# dawn.net
KiCad netlist of a schematic drawn in EAGLE
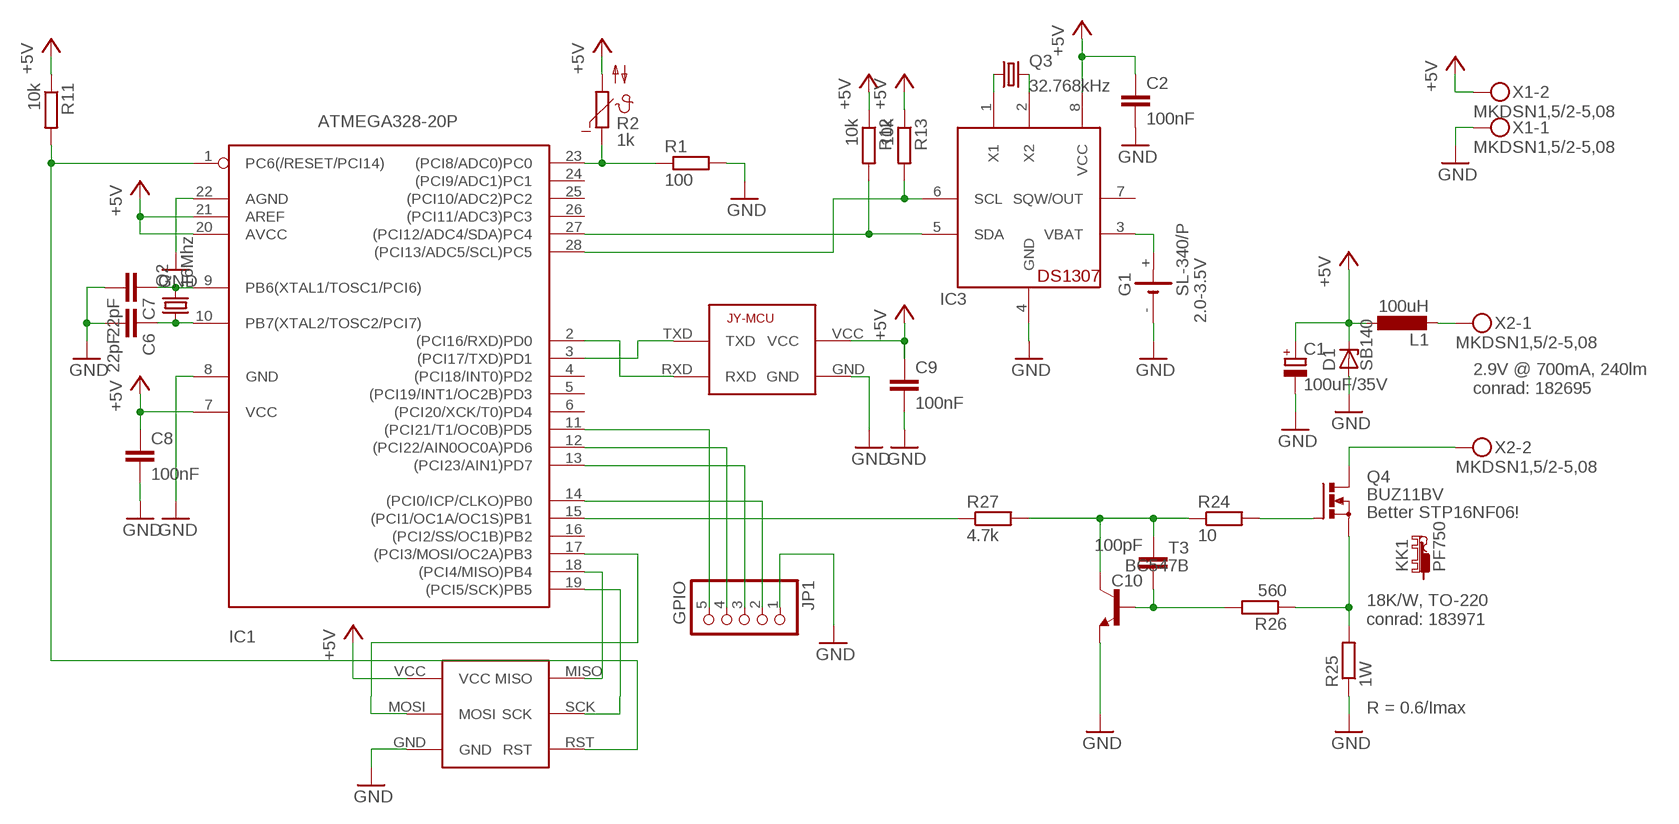
[diagram p0: schematic, sheet 1]

(export (version "E")
  (design (tool "Eeschema 10.0.6"))
  (components
    (comp (ref "C1")
      (value "100uF/35V")
      (footprint "eagle-import:E5-6")
      (libsource (lib "eagle-import") (part "CPOL-EUE5-6"))
    )
    (comp (ref "C2")
      (value "100nF")
      (footprint "eagle-import:C025-025X050")
      (libsource (lib "eagle-import") (part "C-EU025-025X050"))
    )
    (comp (ref "C6")
      (value "22pF")
      (footprint "eagle-import:C050-025X075")
      (libsource (lib "eagle-import") (part "C-EU050-025X075"))
    )
    (comp (ref "C7")
      (value "22pF")
      (footprint "eagle-import:C025-025X050")
      (libsource (lib "eagle-import") (part "C-EU025-025X050"))
    )
    (comp (ref "C8")
      (value "100nF")
      (footprint "eagle-import:C025-025X050")
      (libsource (lib "eagle-import") (part "C-EU025-025X050"))
    )
    (comp (ref "C9")
      (value "100nF")
      (footprint "eagle-import:C025-025X050")
      (libsource (lib "eagle-import") (part "C-EU025-025X050"))
    )
    (comp (ref "C10")
      (value "100pF")
      (footprint "eagle-import:C025-025X050")
      (libsource (lib "eagle-import") (part "C-EU025-025X050"))
    )
    (comp (ref "D1")
      (value "SB140")
      (footprint "eagle-import:DO35Z10")
      (libsource (lib "eagle-import") (part "ZENER-DIODEDO35Z10"))
    )
    (comp (ref "G1")
      (value "SL-340/P")
      (footprint "eagle-import:BEL_P")
      (libsource (lib "eagle-import") (part "SL-340/P"))
    )
    (comp (ref "IC1")
      (value "ATMEGA328-20P")
      (footprint "eagle-import:DIL28-3")
      (libsource (lib "eagle-import") (part "ATMEGA328P-20"))
    )
    (comp (ref "IC3")
      (value "DS1307")
      (footprint "eagle-import:DIL08")
      (libsource (lib "eagle-import") (part "DS1307"))
    )
    (comp (ref "JP1")
      (value "GPIO")
      (footprint "eagle-import:1X05")
      (libsource (lib "eagle-import") (part "PINHD-1X5"))
    )
    (comp (ref "KK1")
      (value "PF750")
      (footprint "eagle-import:PF752")
      (libsource (lib "eagle-import") (part "PF750"))
    )
    (comp (ref "L1")
      (value "100uH")
      (footprint "eagle-import:6000-XXXX-RC")
      (libsource (lib "eagle-import") (part "L-EU6000-XXX-RC"))
    )
    (comp (ref "Q2")
      (value "16Mhz")
      (footprint "eagle-import:HC18U-V")
      (libsource (lib "eagle-import") (part "CRYSTALHC18U-V"))
    )
    (comp (ref "Q3")
      (value "32.768kHz")
      (footprint "eagle-import:TC26V")
      (libsource (lib "eagle-import") (part "CRYSTALTC26V"))
    )
    (comp (ref "Q4")
      (value "BUZ11BV")
      (footprint "eagle-import:TO220BV")
      (libsource (lib "eagle-import") (part "BUZ11BV"))
    )
    (comp (ref "R1")
      (value "100")
      (footprint "eagle-import:0204V")
      (libsource (lib "eagle-import") (part "R-EU_0204/2V"))
    )
    (comp (ref "R2")
      (value "1k")
      (footprint "eagle-import:B57164")
      (fields (field (name "MPN") "B57164K474K52"))
      (libsource (lib "eagle-import") (part "B57164"))
    )
    (comp (ref "R11")
      (value "10k")
      (footprint "eagle-import:0207_10")
      (libsource (lib "eagle-import") (part "R-EU_0207/10"))
    )
    (comp (ref "R12")
      (value "10k")
      (footprint "eagle-import:0204_5")
      (libsource (lib "eagle-import") (part "R-EU_0204/5"))
    )
    (comp (ref "R13")
      (value "10k")
      (footprint "eagle-import:0204V")
      (libsource (lib "eagle-import") (part "R-EU_0204/2V"))
    )
    (comp (ref "R24")
      (value "10")
      (footprint "eagle-import:0204_7")
      (libsource (lib "eagle-import") (part "R-EU_0204/7"))
    )
    (comp (ref "R25")
      (value "1W")
      (footprint "eagle-import:0411_12")
      (libsource (lib "eagle-import") (part "R-EU_0411/12"))
    )
    (comp (ref "R26")
      (value "560")
      (footprint "eagle-import:0207_17")
      (libsource (lib "eagle-import") (part "R-EU_0207/17"))
    )
    (comp (ref "R27")
      (value "4.7k")
      (footprint "eagle-import:0207_10")
      (libsource (lib "eagle-import") (part "R-EU_0207/10"))
    )
    (comp (ref "T3")
      (value "BC547B")
      (footprint "eagle-import:TO92-EBC")
      (libsource (lib "eagle-import") (part "-NPN-TO92-EBC"))
    )
    (comp (ref "U$1")
      (value "JY-MCU")
      (footprint "eagle-import:JY-MCU")
      (libsource (lib "eagle-import") (part "JY-MCU"))
    )
    (comp (ref "U$2")
      (value "AVR-ISP")
      (footprint "eagle-import:AVR-ISP")
      (libsource (lib "eagle-import") (part "AVR-ISP"))
    )
    (comp (ref "X1")
      (value "MKDSN1,5/2-5,08")
      (footprint "eagle-import:MKDSN1,5_2-5,08")
      (libsource (lib "eagle-import") (part "MKDSN1,5/2-5,08"))
    )
    (comp (ref "X2")
      (value "MKDSN1,5/2-5,08")
      (footprint "eagle-import:MKDSN1,5_2-5,08")
      (libsource (lib "eagle-import") (part "MKDSN1,5/2-5,08"))
    )
  )
  (nets
    (net (code "1") (name "+5V") (class "Default")
      (node (ref "C1") (pin "+") (pinfunction "+_+") (pintype "passive"))
      (node (ref "C2") (pin "1") (pinfunction "1_1") (pintype "passive"))
      (node (ref "C8") (pin "1") (pinfunction "1_1") (pintype "passive"))
      (node (ref "C9") (pin "1") (pinfunction "1_1") (pintype "passive"))
      (node (ref "D1") (pin "C") (pinfunction "C_C") (pintype "passive"))
      (node (ref "IC1") (pin "20") (pinfunction "AVCC_20") (pintype "bidirectional"))
      (node (ref "IC1") (pin "21") (pinfunction "AREF_21") (pintype "bidirectional"))
      (node (ref "IC1") (pin "7") (pinfunction "VCC_7") (pintype "bidirectional"))
      (node (ref "IC3") (pin "8") (pinfunction "VCC_8") (pintype "power_in"))
      (node (ref "L1") (pin "1") (pinfunction "1_1") (pintype "passive"))
      (node (ref "R11") (pin "1") (pinfunction "1_1") (pintype "passive"))
      (node (ref "R12") (pin "1") (pinfunction "1_1") (pintype "passive"))
      (node (ref "R13") (pin "1") (pinfunction "1_1") (pintype "passive"))
      (node (ref "R2") (pin "2") (pinfunction "2_2") (pintype "passive"))
      (node (ref "U$1") (pin "VCC") (pinfunction "VCC_VCC") (pintype "bidirectional"))
      (node (ref "U$2") (pin "VCC") (pinfunction "VCC_VCC") (pintype "bidirectional"))
      (node (ref "X1") (pin "2") (pinfunction "KL_2") (pintype "passive"))
    )
    (net (code "2") (name "GND") (class "Default")
      (node (ref "C1") (pin "-") (pinfunction "-_-") (pintype "passive"))
      (node (ref "C2") (pin "2") (pinfunction "2_2") (pintype "passive"))
      (node (ref "C6") (pin "2") (pinfunction "2_2") (pintype "passive"))
      (node (ref "C7") (pin "2") (pinfunction "2_2") (pintype "passive"))
      (node (ref "C8") (pin "2") (pinfunction "2_2") (pintype "passive"))
      (node (ref "C9") (pin "2") (pinfunction "2_2") (pintype "passive"))
      (node (ref "D1") (pin "A") (pinfunction "A_A") (pintype "passive"))
      (node (ref "G1") (pin "-") (pinfunction "-_-") (pintype "passive"))
      (node (ref "IC1") (pin "22") (pinfunction "AGND_22") (pintype "bidirectional"))
      (node (ref "IC1") (pin "8") (pinfunction "GND_8") (pintype "bidirectional"))
      (node (ref "IC3") (pin "4") (pinfunction "GND_4") (pintype "power_in"))
      (node (ref "JP1") (pin "1") (pinfunction "1_1") (pintype "passive"))
      (node (ref "R1") (pin "2") (pinfunction "2_2") (pintype "passive"))
      (node (ref "R25") (pin "1") (pinfunction "1_1") (pintype "passive"))
      (node (ref "T3") (pin "E") (pinfunction "E_E") (pintype "passive"))
      (node (ref "U$1") (pin "GND") (pinfunction "GND_GND") (pintype "bidirectional"))
      (node (ref "U$2") (pin "GND") (pinfunction "GND_GND") (pintype "bidirectional"))
      (node (ref "X1") (pin "1") (pinfunction "KL_1") (pintype "passive"))
    )
    (net (code "3") (name "Net-(C10-Pad1)") (class "Default")
      (node (ref "C10") (pin "1") (pinfunction "1_1") (pintype "passive"))
      (node (ref "R26") (pin "2") (pinfunction "2_2") (pintype "passive"))
      (node (ref "T3") (pin "B") (pinfunction "B_B") (pintype "passive"))
    )
    (net (code "4") (name "Net-(C10-Pad2)") (class "Default")
      (node (ref "C10") (pin "2") (pinfunction "2_2") (pintype "passive"))
      (node (ref "R24") (pin "1") (pinfunction "1_1") (pintype "passive"))
      (node (ref "R27") (pin "2") (pinfunction "2_2") (pintype "passive"))
      (node (ref "T3") (pin "C") (pinfunction "C_C") (pintype "passive"))
    )
    (net (code "5") (name "Net-(IC1-(PCI0{slash}ICP{slash}CLKO)PB0)") (class "Default")
      (node (ref "IC1") (pin "14") (pinfunction "(PCI0/ICP/CLKO)PB0_14") (pintype "bidirectional"))
      (node (ref "JP1") (pin "2") (pinfunction "2_2") (pintype "passive"))
    )
    (net (code "6") (name "Net-(IC1-(PCI1{slash}OC1A{slash}OC1S)PB1)") (class "Default")
      (node (ref "IC1") (pin "15") (pinfunction "(PCI1/OC1A/OC1S)PB1_15") (pintype "bidirectional"))
      (node (ref "R27") (pin "1") (pinfunction "1_1") (pintype "passive"))
    )
    (net (code "7") (name "Net-(IC1-(PCI3{slash}MOSI{slash}OC2A)PB3)") (class "Default")
      (node (ref "IC1") (pin "17") (pinfunction "(PCI3/MOSI/OC2A)PB3_17") (pintype "bidirectional"))
      (node (ref "U$2") (pin "MOSI") (pinfunction "MOSI_MOSI") (pintype "bidirectional"))
    )
    (net (code "8") (name "Net-(IC1-(PCI4{slash}MISO)PB4)") (class "Default")
      (node (ref "IC1") (pin "18") (pinfunction "(PCI4/MISO)PB4_18") (pintype "bidirectional"))
      (node (ref "U$2") (pin "MISO") (pinfunction "MISO_MISO") (pintype "bidirectional"))
    )
    (net (code "9") (name "Net-(IC1-(PCI5{slash}SCK)PB5)") (class "Default")
      (node (ref "IC1") (pin "19") (pinfunction "(PCI5/SCK)PB5_19") (pintype "bidirectional"))
      (node (ref "U$2") (pin "SCK") (pinfunction "SCK_SCK") (pintype "bidirectional"))
    )
    (net (code "10") (name "Net-(IC1-(PCI8{slash}ADC0)PC0)") (class "Default")
      (node (ref "IC1") (pin "23") (pinfunction "(PCI8/ADC0)PC0_23") (pintype "bidirectional"))
      (node (ref "R1") (pin "1") (pinfunction "1_1") (pintype "passive"))
      (node (ref "R2") (pin "1") (pinfunction "1_1") (pintype "passive"))
    )
    (net (code "11") (name "Net-(IC1-(PCI12{slash}ADC4{slash}SDA)PC4)") (class "Default")
      (node (ref "IC1") (pin "27") (pinfunction "(PCI12/ADC4/SDA)PC4_27") (pintype "bidirectional"))
      (node (ref "IC3") (pin "5") (pinfunction "SDA_5") (pintype "bidirectional"))
      (node (ref "R12") (pin "2") (pinfunction "2_2") (pintype "passive"))
    )
    (net (code "12") (name "Net-(IC1-(PCI13{slash}ADC5{slash}SCL)PC5)") (class "Default")
      (node (ref "IC1") (pin "28") (pinfunction "(PCI13/ADC5/SCL)PC5_28") (pintype "bidirectional"))
      (node (ref "IC3") (pin "6") (pinfunction "SCL_6") (pintype "bidirectional"))
      (node (ref "R13") (pin "2") (pinfunction "2_2") (pintype "passive"))
    )
    (net (code "13") (name "Net-(IC1-(PCI16{slash}RXD)PD0)") (class "Default")
      (node (ref "IC1") (pin "2") (pinfunction "(PCI16/RXD)PD0_2") (pintype "bidirectional"))
      (node (ref "U$1") (pin "RXD") (pinfunction "RXD_RXD") (pintype "bidirectional"))
    )
    (net (code "14") (name "Net-(IC1-(PCI17{slash}TXD)PD1)") (class "Default")
      (node (ref "IC1") (pin "3") (pinfunction "(PCI17/TXD)PD1_3") (pintype "bidirectional"))
      (node (ref "U$1") (pin "TXD") (pinfunction "TXD_TXD") (pintype "bidirectional"))
    )
    (net (code "15") (name "Net-(IC1-(PCI21{slash}T1{slash}OC0B)PD5)") (class "Default")
      (node (ref "IC1") (pin "11") (pinfunction "(PCI21/T1/OC0B)PD5_11") (pintype "bidirectional"))
      (node (ref "JP1") (pin "5") (pinfunction "5_5") (pintype "passive"))
    )
    (net (code "16") (name "Net-(IC1-(PCI22{slash}AIN0OC0A)PD6)") (class "Default")
      (node (ref "IC1") (pin "12") (pinfunction "(PCI22/AIN0OC0A)PD6_12") (pintype "bidirectional"))
      (node (ref "JP1") (pin "4") (pinfunction "4_4") (pintype "passive"))
    )
    (net (code "17") (name "Net-(IC1-(PCI23{slash}AIN1)PD7)") (class "Default")
      (node (ref "IC1") (pin "13") (pinfunction "(PCI23/AIN1)PD7_13") (pintype "bidirectional"))
      (node (ref "JP1") (pin "3") (pinfunction "3_3") (pintype "passive"))
    )
    (net (code "18") (name "Net-(IC1-PB6(XTAL1{slash}TOSC1{slash}PCI6))") (class "Default")
      (node (ref "C7") (pin "1") (pinfunction "1_1") (pintype "passive"))
      (node (ref "IC1") (pin "9") (pinfunction "PB6(XTAL1/TOSC1/PCI6)_9") (pintype "bidirectional"))
      (node (ref "Q2") (pin "2") (pinfunction "2_2") (pintype "passive"))
    )
    (net (code "19") (name "Net-(IC1-PB7(XTAL2{slash}TOSC2{slash}PCI7))") (class "Default")
      (node (ref "C6") (pin "1") (pinfunction "1_1") (pintype "passive"))
      (node (ref "IC1") (pin "10") (pinfunction "PB7(XTAL2/TOSC2/PCI7)_10") (pintype "bidirectional"))
      (node (ref "Q2") (pin "1") (pinfunction "1_1") (pintype "passive"))
    )
    (net (code "20") (name "Net-(IC1-PC6({slash}RESET{slash}PCI14))") (class "Default")
      (node (ref "IC1") (pin "1") (pinfunction "PC6(/RESET/PCI14)_1") (pintype "bidirectional"))
      (node (ref "R11") (pin "2") (pinfunction "2_2") (pintype "passive"))
      (node (ref "U$2") (pin "RST") (pinfunction "RST_RST") (pintype "bidirectional"))
    )
    (net (code "21") (name "Net-(IC3-VBAT)") (class "Default")
      (node (ref "G1") (pin "+") (pinfunction "+_+") (pintype "passive"))
      (node (ref "IC3") (pin "3") (pinfunction "VBAT_3") (pintype "power_in"))
    )
    (net (code "22") (name "Net-(IC3-X1)") (class "Default")
      (node (ref "IC3") (pin "1") (pinfunction "X1_1") (pintype "passive"))
      (node (ref "Q3") (pin "1") (pinfunction "1_1") (pintype "passive"))
    )
    (net (code "23") (name "Net-(IC3-X2)") (class "Default")
      (node (ref "IC3") (pin "2") (pinfunction "X2_2") (pintype "passive"))
      (node (ref "Q3") (pin "2") (pinfunction "2_2") (pintype "passive"))
    )
    (net (code "24") (name "Net-(Q4-PadG)") (class "Default")
      (node (ref "Q4") (pin "G") (pinfunction "G_G") (pintype "passive"))
      (node (ref "R24") (pin "2") (pinfunction "2_2") (pintype "passive"))
    )
    (net (code "25") (name "Net-(Q4-PadS)") (class "Default")
      (node (ref "Q4") (pin "S") (pinfunction "S_S") (pintype "passive"))
      (node (ref "R25") (pin "2") (pinfunction "2_2") (pintype "passive"))
      (node (ref "R26") (pin "1") (pinfunction "1_1") (pintype "passive"))
    )
    (net (code "26") (name "Net-(X2A-KL)") (class "Default")
      (node (ref "L1") (pin "2") (pinfunction "2_2") (pintype "passive"))
      (node (ref "X2") (pin "1") (pinfunction "KL_1") (pintype "passive"))
    )
    (net (code "27") (name "Net-(X2B-KL)") (class "Default")
      (node (ref "Q4") (pin "D") (pinfunction "D_D") (pintype "passive"))
      (node (ref "X2") (pin "2") (pinfunction "KL_2") (pintype "passive"))
    )
    (net (code "28") (name "unconnected-(IC1-(PCI2{slash}SS{slash}OC1B)PB2-Pad16)") (class "Default")
      (node (ref "IC1") (pin "16") (pinfunction "(PCI2/SS/OC1B)PB2_16") (pintype "bidirectional"))
    )
    (net (code "29") (name "unconnected-(IC1-(PCI9{slash}ADC1)PC1-Pad24)") (class "Default")
      (node (ref "IC1") (pin "24") (pinfunction "(PCI9/ADC1)PC1_24") (pintype "bidirectional"))
    )
    (net (code "30") (name "unconnected-(IC1-(PCI10{slash}ADC2)PC2-Pad25)") (class "Default")
      (node (ref "IC1") (pin "25") (pinfunction "(PCI10/ADC2)PC2_25") (pintype "bidirectional"))
    )
    (net (code "31") (name "unconnected-(IC1-(PCI11{slash}ADC3)PC3-Pad26)") (class "Default")
      (node (ref "IC1") (pin "26") (pinfunction "(PCI11/ADC3)PC3_26") (pintype "bidirectional"))
    )
    (net (code "32") (name "unconnected-(IC1-(PCI18{slash}INT0)PD2-Pad4)") (class "Default")
      (node (ref "IC1") (pin "4") (pinfunction "(PCI18/INT0)PD2_4") (pintype "bidirectional"))
    )
    (net (code "33") (name "unconnected-(IC1-(PCI19{slash}INT1{slash}OC2B)PD3-Pad5)") (class "Default")
      (node (ref "IC1") (pin "5") (pinfunction "(PCI19/INT1/OC2B)PD3_5") (pintype "bidirectional"))
    )
    (net (code "34") (name "unconnected-(IC1-(PCI20{slash}XCK{slash}T0)PD4-Pad6)") (class "Default")
      (node (ref "IC1") (pin "6") (pinfunction "(PCI20/XCK/T0)PD4_6") (pintype "bidirectional"))
    )
    (net (code "35") (name "unconnected-(IC3-SQW{slash}OUT-Pad7)") (class "Default")
      (node (ref "IC3") (pin "7") (pinfunction "SQW/OUT_7") (pintype "bidirectional"))
    )
  )
)
